# LG_TRACKER_IO_Expanders.net
KiCad netlist of a schematic drawn in Altium Designer
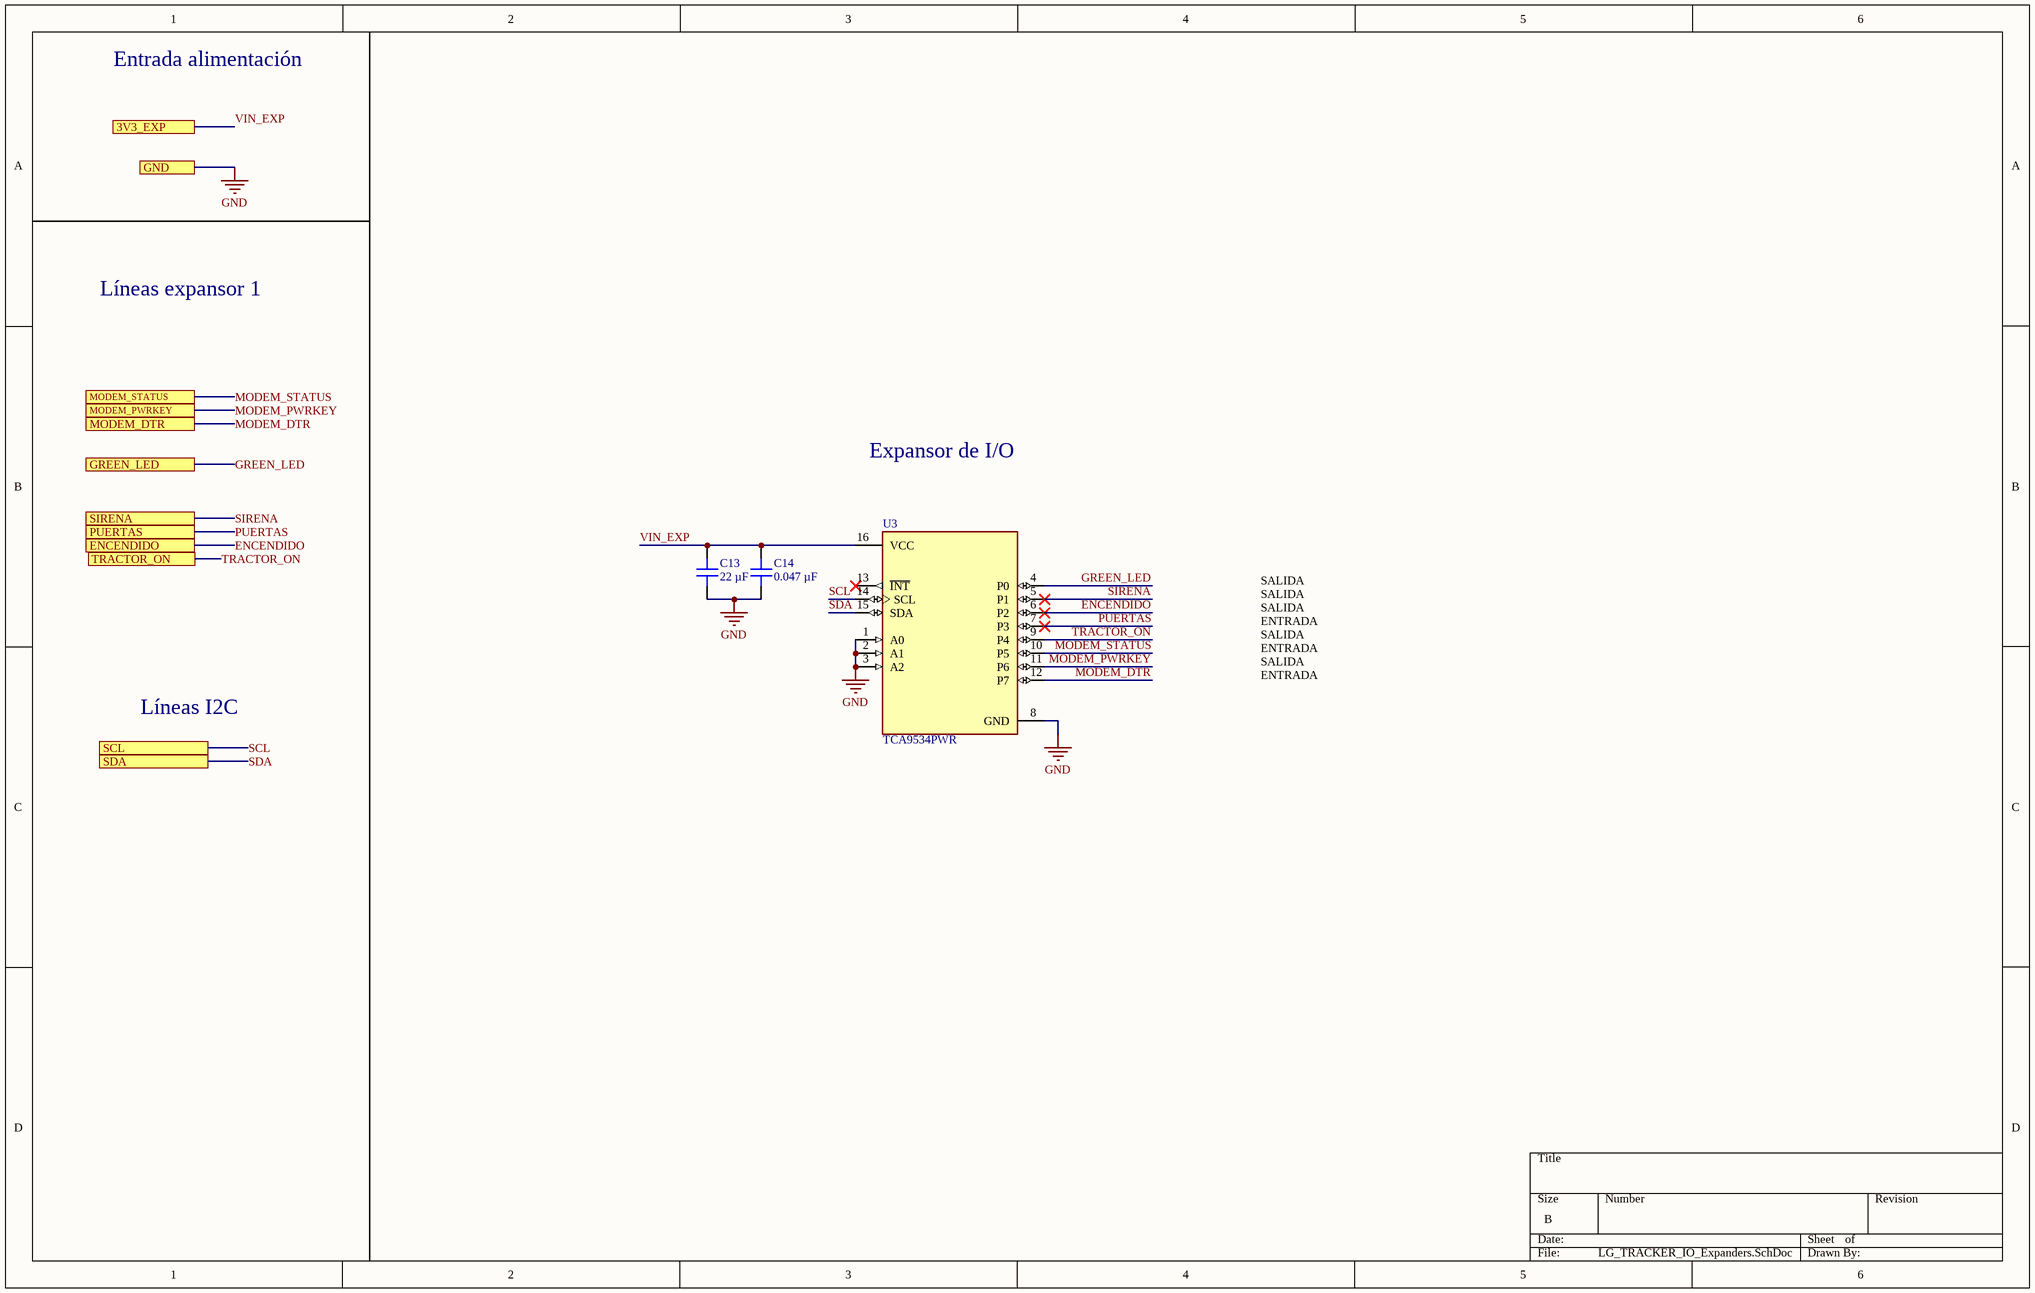
[diagram p0: LG_TRACKER_IO_Expanders.SchDoc]

(export (version "E")
  (design (tool "Eeschema 10.0.6"))
  (components
    (comp (ref "C13")
      (value "22 µF")
      (footprint "CAP 0805_2012")
      (description "CAP CER 22UF 16V X5R 0805")
      (fields
        (field (name "PART NUMBER") "CL21A226MOCLRNC")
        (field (name "MANUFACTURER") "Samsung Electro-Mechanics")
      )
      (libsource (lib "Celestial Altium Library - altium_library") (part "Capacitor"))
    )
    (comp (ref "C14")
      (value "0.047 µF")
      (footprint "CAP 0603_1608")
      (description "CAP CER 0.047UF 100V X7R 0603")
      (fields (field (name "PART NUMBER") "885012206118") (field (name "MANUFACTURER") "Würth Elektronik"))
      (libsource (lib "Celestial Altium Library - altium_library") (part "Capacitor"))
    )
    (comp (ref "U3")
      (value "TCA9534PWR")
      (footprint "16-TSSOP")
      (libsource (lib "DIN_DC_Base_Board_components") (part "TCA9534PWR"))
    )
  )
  (nets
    (net (code "1") (name "/ENCENDIDO") (class "Default")
      (node (ref "U3") (pin "6") (pinfunction "P2_6") (pintype "bidirectional"))
    )
    (net (code "2") (name "/GREEN_LED") (class "Default")
      (node (ref "U3") (pin "4") (pinfunction "P0_4") (pintype "bidirectional"))
    )
    (net (code "3") (name "/MODEM_DTR") (class "Default")
      (node (ref "U3") (pin "12") (pinfunction "P7_12") (pintype "bidirectional"))
    )
    (net (code "4") (name "/MODEM_PWRKEY") (class "Default")
      (node (ref "U3") (pin "11") (pinfunction "P6_11") (pintype "bidirectional"))
    )
    (net (code "5") (name "/MODEM_STATUS") (class "Default")
      (node (ref "U3") (pin "10") (pinfunction "P5_10") (pintype "bidirectional"))
    )
    (net (code "6") (name "/PUERTAS") (class "Default")
      (node (ref "U3") (pin "7") (pinfunction "P3_7") (pintype "bidirectional"))
    )
    (net (code "7") (name "/SCL") (class "Default")
      (node (ref "U3") (pin "14") (pinfunction "SCL_14") (pintype "bidirectional"))
    )
    (net (code "8") (name "/SDA") (class "Default")
      (node (ref "U3") (pin "15") (pinfunction "SDA_15") (pintype "bidirectional"))
    )
    (net (code "9") (name "/SIRENA") (class "Default")
      (node (ref "U3") (pin "5") (pinfunction "P1_5") (pintype "bidirectional"))
    )
    (net (code "10") (name "/TRACTOR_ON") (class "Default")
      (node (ref "U3") (pin "9") (pinfunction "P4_9") (pintype "bidirectional"))
    )
    (net (code "11") (name "/VIN_EXP") (class "Default")
      (node (ref "C13") (pin "2") (pinfunction "2_2") (pintype "passive"))
      (node (ref "C14") (pin "2") (pinfunction "2_2") (pintype "passive"))
      (node (ref "U3") (pin "16") (pinfunction "VCC_16") (pintype "power_in"))
    )
    (net (code "12") (name "GND") (class "Default")
      (node (ref "C13") (pin "1") (pinfunction "1_1") (pintype "passive"))
      (node (ref "C14") (pin "1") (pinfunction "1_1") (pintype "passive"))
      (node (ref "U3") (pin "1") (pinfunction "A0_1") (pintype "input"))
      (node (ref "U3") (pin "2") (pinfunction "A1_2") (pintype "input"))
      (node (ref "U3") (pin "3") (pinfunction "A2_3") (pintype "input"))
      (node (ref "U3") (pin "8") (pinfunction "GND_8") (pintype "power_in"))
    )
    (net (code "13") (name "unconnected-(U3-~{INT}-Pad13)") (class "Default")
      (node (ref "U3") (pin "13") (pinfunction "~{INT}_13") (pintype "output+no_connect"))
    )
  )
)
